# 22_Power_Ext_Discrete_RTC_IC.net
KiCad netlist of a schematic drawn in Altium Designer
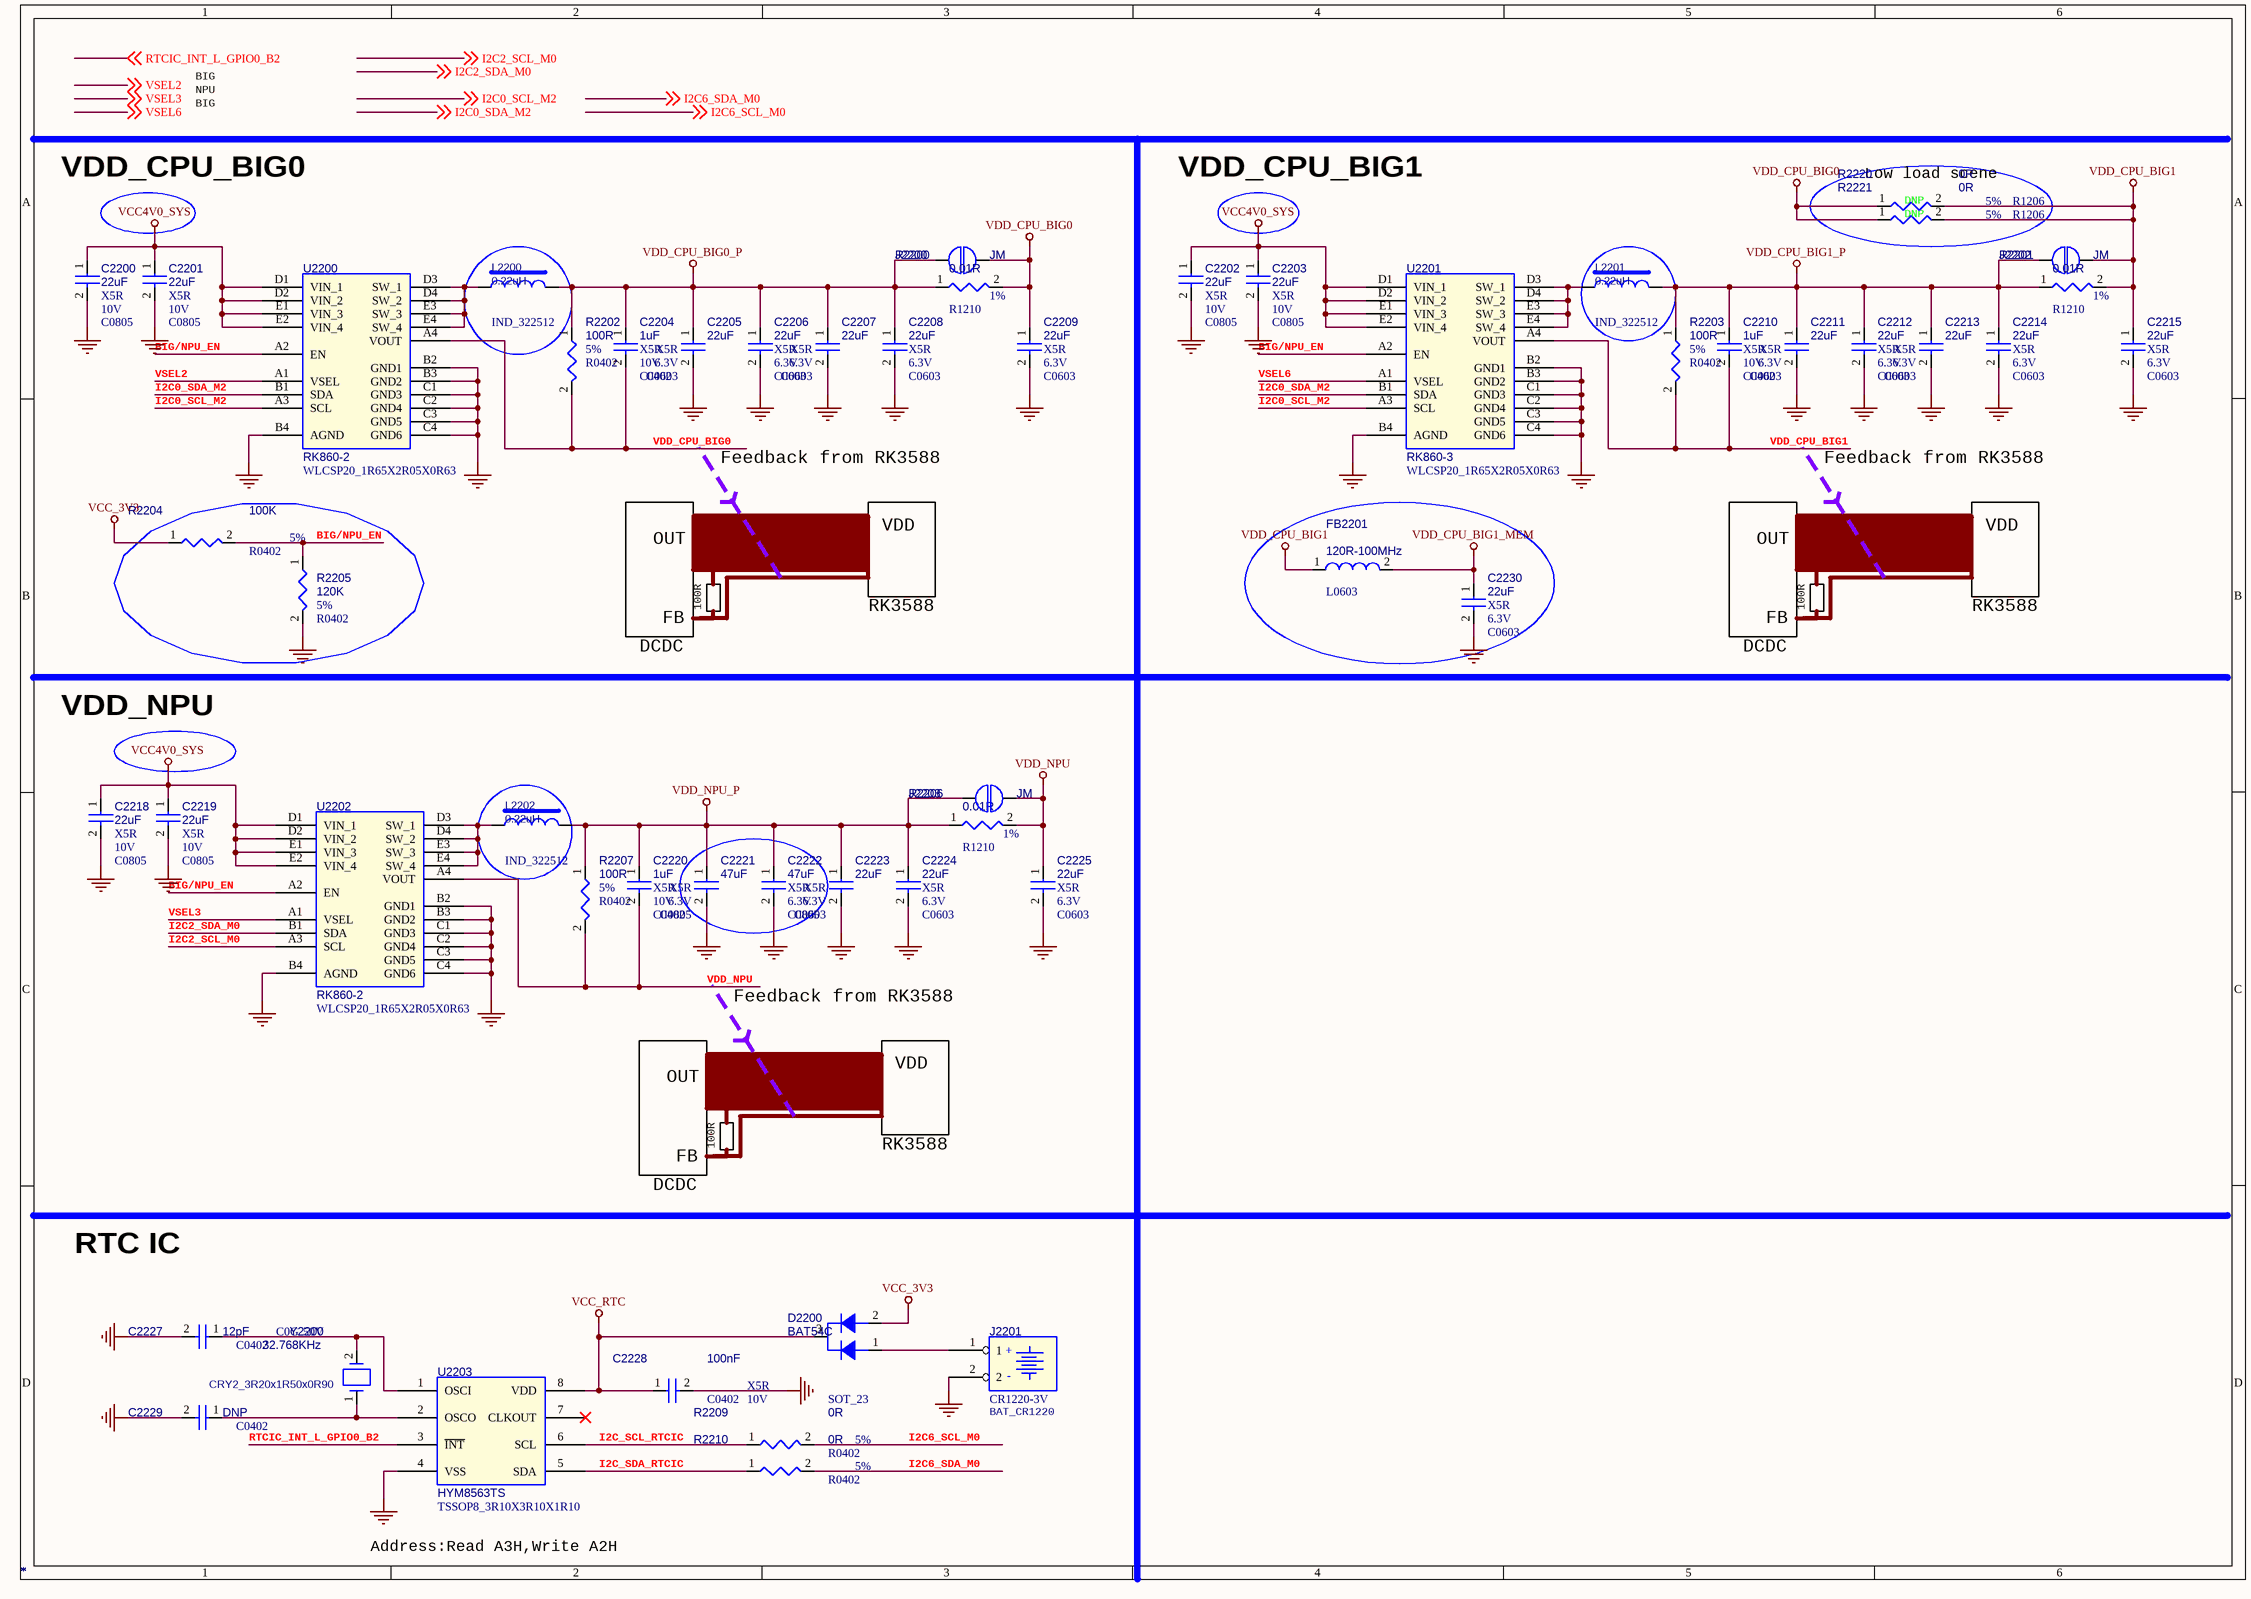
[diagram p0: 22.Power_Ext Discrete_RTC IC.SchDoc]

(export (version "E")
  (design (tool "Eeschema 10.0.6"))
  (components
    (comp (ref "C2200")
      (value "*")
      (footprint "C0805")
      (description "cap,22.00uF,+/-10%,10V,X5R,C0805")
      (fields
        (field (name "VOLTAGE") "10V")
        (field (name "PCB FOOTPRINT") "C0805")
        (field (name "DIELECTRIC") "X5R")
        (field (name "MANUFACTURER") "TDK")
        (field (name "TOLERANCE") "10%")
        (field (name "ALTIUM_UNNAMED_1") "22uF")
        (field (name "CREATED BY") "JJJ")
      )
      (libsource (lib "*") (part "CAP NP"))
    )
    (comp (ref "C2201")
      (value "*")
      (footprint "C0805")
      (description "cap,22.00uF,+/-10%,10V,X5R,C0805")
      (fields
        (field (name "VOLTAGE") "10V")
        (field (name "PCB FOOTPRINT") "C0805")
        (field (name "DIELECTRIC") "X5R")
        (field (name "MANUFACTURER") "TDK")
        (field (name "TOLERANCE") "10%")
        (field (name "ALTIUM_UNNAMED_1") "22uF")
        (field (name "CREATED BY") "JJJ")
      )
      (libsource (lib "*") (part "CAP NP"))
    )
    (comp (ref "C2202")
      (value "*")
      (footprint "C0805")
      (description "cap,22.00uF,+/-10%,10V,X5R,C0805")
      (fields
        (field (name "VOLTAGE") "10V")
        (field (name "PCB FOOTPRINT") "C0805")
        (field (name "DIELECTRIC") "X5R")
        (field (name "MANUFACTURER") "TDK")
        (field (name "TOLERANCE") "10%")
        (field (name "ALTIUM_UNNAMED_1") "22uF")
        (field (name "CREATED BY") "JJJ")
      )
      (libsource (lib "*") (part "CAP NP"))
    )
    (comp (ref "C2203")
      (value "*")
      (footprint "C0805")
      (description "cap,22.00uF,+/-10%,10V,X5R,C0805")
      (fields
        (field (name "VOLTAGE") "10V")
        (field (name "PCB FOOTPRINT") "C0805")
        (field (name "DIELECTRIC") "X5R")
        (field (name "MANUFACTURER") "TDK")
        (field (name "TOLERANCE") "10%")
        (field (name "ALTIUM_UNNAMED_1") "22uF")
        (field (name "CREATED BY") "JJJ")
      )
      (libsource (lib "*") (part "CAP NP"))
    )
    (comp (ref "C2204")
      (value "*")
      (footprint "C0402")
      (description "cap,1.00uF,+/-10%,10V,X5R,C0402")
      (fields
        (field (name "VOLTAGE") "10V")
        (field (name "PCB FOOTPRINT") "C0402")
        (field (name "DIELECTRIC") "X5R")
        (field (name "TOLERANCE") "10%")
        (field (name "MANUFACTURER") "TDK")
        (field (name "ALTIUM_UNNAMED_1") "1uF")
        (field (name "CREATED BY") "JJJ")
      )
      (libsource (lib "*") (part "CAP NP"))
    )
    (comp (ref "C2205")
      (value "*")
      (footprint "C0603")
      (description "cap,22.00uF,+/-20%,6.3V,X5R,C0603")
      (fields
        (field (name "VOLTAGE") "6.3V")
        (field (name "PCB FOOTPRINT") "C0603")
        (field (name "DIELECTRIC") "X5R")
        (field (name "TOLERANCE") "20%")
        (field (name "MANUFACTURER") "TDK")
        (field (name "ALTIUM_UNNAMED_1") "22uF")
        (field (name "CREATED BY") "JJJ")
      )
      (libsource (lib "*") (part "CAP NP"))
    )
    (comp (ref "C2206")
      (value "*")
      (footprint "C0603")
      (description "cap,22.00uF,+/-20%,6.3V,X5R,C0603")
      (fields
        (field (name "VOLTAGE") "6.3V")
        (field (name "PCB FOOTPRINT") "C0603")
        (field (name "DIELECTRIC") "X5R")
        (field (name "MANUFACTURER") "TDK")
        (field (name "TOLERANCE") "20%")
        (field (name "ALTIUM_UNNAMED_1") "22uF")
        (field (name "CREATED BY") "JJJ")
      )
      (libsource (lib "*") (part "CAP NP"))
    )
    (comp (ref "C2207")
      (value "*")
      (footprint "C0603")
      (description "cap,22.00uF,+/-20%,6.3V,X5R,C0603")
      (fields
        (field (name "VOLTAGE") "6.3V")
        (field (name "PCB FOOTPRINT") "C0603")
        (field (name "DIELECTRIC") "X5R")
        (field (name "MANUFACTURER") "TDK")
        (field (name "TOLERANCE") "20%")
        (field (name "ALTIUM_UNNAMED_1") "22uF")
        (field (name "CREATED BY") "JJJ")
      )
      (libsource (lib "*") (part "CAP NP"))
    )
    (comp (ref "C2208")
      (value "*")
      (footprint "C0603")
      (description "cap,22.00uF,+/-20%,6.3V,X5R,C0603")
      (fields
        (field (name "VOLTAGE") "6.3V")
        (field (name "PCB FOOTPRINT") "C0603")
        (field (name "DIELECTRIC") "X5R")
        (field (name "MANUFACTURER") "TDK")
        (field (name "TOLERANCE") "20%")
        (field (name "ALTIUM_UNNAMED_1") "22uF")
        (field (name "CREATED BY") "JJJ")
      )
      (libsource (lib "*") (part "CAP NP"))
    )
    (comp (ref "C2209")
      (value "*")
      (footprint "C0603")
      (description "cap,22.00uF,+/-20%,6.3V,X5R,C0603")
      (fields
        (field (name "VOLTAGE") "6.3V")
        (field (name "PCB FOOTPRINT") "C0603")
        (field (name "DIELECTRIC") "X5R")
        (field (name "TOLERANCE") "20%")
        (field (name "MANUFACTURER") "TDK")
        (field (name "ALTIUM_UNNAMED_1") "22uF")
        (field (name "CREATED BY") "JJJ")
      )
      (libsource (lib "*") (part "CAP NP"))
    )
    (comp (ref "C2210")
      (value "*")
      (footprint "C0402")
      (description "cap,1.00uF,+/-10%,10V,X5R,C0402")
      (fields
        (field (name "VOLTAGE") "10V")
        (field (name "PCB FOOTPRINT") "C0402")
        (field (name "DIELECTRIC") "X5R")
        (field (name "TOLERANCE") "10%")
        (field (name "MANUFACTURER") "TDK")
        (field (name "ALTIUM_UNNAMED_1") "1uF")
        (field (name "CREATED BY") "JJJ")
      )
      (libsource (lib "*") (part "CAP NP"))
    )
    (comp (ref "C2211")
      (value "*")
      (footprint "C0603")
      (description "cap,22.00uF,+/-20%,6.3V,X5R,C0603")
      (fields
        (field (name "VOLTAGE") "6.3V")
        (field (name "PCB FOOTPRINT") "C0603")
        (field (name "DIELECTRIC") "X5R")
        (field (name "TOLERANCE") "20%")
        (field (name "MANUFACTURER") "TDK")
        (field (name "ALTIUM_UNNAMED_1") "22uF")
        (field (name "CREATED BY") "JJJ")
      )
      (libsource (lib "*") (part "CAP NP"))
    )
    (comp (ref "C2212")
      (value "*")
      (footprint "C0603")
      (description "cap,22.00uF,+/-20%,6.3V,X5R,C0603")
      (fields
        (field (name "VOLTAGE") "6.3V")
        (field (name "PCB FOOTPRINT") "C0603")
        (field (name "DIELECTRIC") "X5R")
        (field (name "MANUFACTURER") "TDK")
        (field (name "TOLERANCE") "20%")
        (field (name "ALTIUM_UNNAMED_1") "22uF")
        (field (name "CREATED BY") "JJJ")
      )
      (libsource (lib "*") (part "CAP NP"))
    )
    (comp (ref "C2213")
      (value "*")
      (footprint "C0603")
      (description "cap,22.00uF,+/-20%,6.3V,X5R,C0603")
      (fields
        (field (name "VOLTAGE") "6.3V")
        (field (name "PCB FOOTPRINT") "C0603")
        (field (name "DIELECTRIC") "X5R")
        (field (name "MANUFACTURER") "TDK")
        (field (name "TOLERANCE") "20%")
        (field (name "ALTIUM_UNNAMED_1") "22uF")
        (field (name "CREATED BY") "JJJ")
      )
      (libsource (lib "*") (part "CAP NP"))
    )
    (comp (ref "C2214")
      (value "*")
      (footprint "C0603")
      (description "cap,22.00uF,+/-20%,6.3V,X5R,C0603")
      (fields
        (field (name "VOLTAGE") "6.3V")
        (field (name "PCB FOOTPRINT") "C0603")
        (field (name "DIELECTRIC") "X5R")
        (field (name "MANUFACTURER") "TDK")
        (field (name "TOLERANCE") "20%")
        (field (name "ALTIUM_UNNAMED_1") "22uF")
        (field (name "CREATED BY") "JJJ")
      )
      (libsource (lib "*") (part "CAP NP"))
    )
    (comp (ref "C2215")
      (value "*")
      (footprint "C0603")
      (description "cap,22.00uF,+/-20%,6.3V,X5R,C0603")
      (fields
        (field (name "VOLTAGE") "6.3V")
        (field (name "PCB FOOTPRINT") "C0603")
        (field (name "DIELECTRIC") "X5R")
        (field (name "TOLERANCE") "20%")
        (field (name "MANUFACTURER") "TDK")
        (field (name "ALTIUM_UNNAMED_1") "22uF")
        (field (name "CREATED BY") "JJJ")
      )
      (libsource (lib "*") (part "CAP NP"))
    )
    (comp (ref "C2218")
      (value "*")
      (footprint "C0805")
      (description "cap,22.00uF,+/-10%,10V,X5R,C0805")
      (fields
        (field (name "VOLTAGE") "10V")
        (field (name "PCB FOOTPRINT") "C0805")
        (field (name "DIELECTRIC") "X5R")
        (field (name "TOLERANCE") "10%")
        (field (name "MANUFACTURER") "TDK")
        (field (name "ALTIUM_UNNAMED_1") "22uF")
        (field (name "CREATED BY") "JJJ")
      )
      (libsource (lib "*") (part "CAP NP"))
    )
    (comp (ref "C2219")
      (value "*")
      (footprint "C0805")
      (description "cap,22.00uF,+/-10%,10V,X5R,C0805")
      (fields
        (field (name "VOLTAGE") "10V")
        (field (name "PCB FOOTPRINT") "C0805")
        (field (name "DIELECTRIC") "X5R")
        (field (name "TOLERANCE") "10%")
        (field (name "MANUFACTURER") "TDK")
        (field (name "ALTIUM_UNNAMED_1") "22uF")
        (field (name "CREATED BY") "JJJ")
      )
      (libsource (lib "*") (part "CAP NP"))
    )
    (comp (ref "C2220")
      (value "*")
      (footprint "C0402")
      (description "cap,1.00uF,+/-10%,10V,X5R,C0402")
      (fields
        (field (name "VOLTAGE") "10V")
        (field (name "PCB FOOTPRINT") "C0402")
        (field (name "DIELECTRIC") "X5R")
        (field (name "MANUFACTURER") "TDK")
        (field (name "TOLERANCE") "10%")
        (field (name "ALTIUM_UNNAMED_1") "1uF")
        (field (name "CREATED BY") "JJJ")
      )
      (libsource (lib "*") (part "CAP NP"))
    )
    (comp (ref "C2221")
      (value "*")
      (footprint "C0805")
      (description "cap,47.00uF,+/-20%,6.3V,X5R,C0805")
      (fields
        (field (name "VOLTAGE") "6.3V")
        (field (name "PCB FOOTPRINT") "C0805")
        (field (name "DIELECTRIC") "X5R")
        (field (name "MANUFACTURER") "TDK")
        (field (name "TOLERANCE") "20%")
        (field (name "ALTIUM_UNNAMED_1") "47uF")
        (field (name "CREATED BY") "JJJ")
      )
      (libsource (lib "*") (part "CAP NP"))
    )
    (comp (ref "C2222")
      (value "*")
      (footprint "C0805")
      (description "cap,47.00uF,+/-20%,6.3V,X5R,C0805")
      (fields
        (field (name "VOLTAGE") "6.3V")
        (field (name "PCB FOOTPRINT") "C0805")
        (field (name "DIELECTRIC") "X5R")
        (field (name "TOLERANCE") "20%")
        (field (name "MANUFACTURER") "TDK")
        (field (name "ALTIUM_UNNAMED_1") "47uF")
        (field (name "CREATED BY") "JJJ")
      )
      (libsource (lib "*") (part "CAP NP"))
    )
    (comp (ref "C2223")
      (value "*")
      (footprint "C0603")
      (description "cap,22.00uF,+/-20%,6.3V,X5R,C0603")
      (fields
        (field (name "VOLTAGE") "6.3V")
        (field (name "PCB FOOTPRINT") "C0603")
        (field (name "DIELECTRIC") "X5R")
        (field (name "TOLERANCE") "20%")
        (field (name "MANUFACTURER") "TDK")
        (field (name "ALTIUM_UNNAMED_1") "22uF")
        (field (name "CREATED BY") "JJJ")
      )
      (libsource (lib "*") (part "CAP NP"))
    )
    (comp (ref "C2224")
      (value "*")
      (footprint "C0603")
      (description "cap,22.00uF,+/-20%,6.3V,X5R,C0603")
      (fields
        (field (name "VOLTAGE") "6.3V")
        (field (name "PCB FOOTPRINT") "C0603")
        (field (name "DIELECTRIC") "X5R")
        (field (name "TOLERANCE") "20%")
        (field (name "MANUFACTURER") "TDK")
        (field (name "ALTIUM_UNNAMED_1") "22uF")
        (field (name "CREATED BY") "JJJ")
      )
      (libsource (lib "*") (part "CAP NP"))
    )
    (comp (ref "C2225")
      (value "*")
      (footprint "C0603")
      (description "cap,22.00uF,+/-20%,6.3V,X5R,C0603")
      (fields
        (field (name "VOLTAGE") "6.3V")
        (field (name "PCB FOOTPRINT") "C0603")
        (field (name "DIELECTRIC") "X5R")
        (field (name "TOLERANCE") "20%")
        (field (name "MANUFACTURER") "TDK")
        (field (name "ALTIUM_UNNAMED_1") "22uF")
        (field (name "CREATED BY") "JJJ")
      )
      (libsource (lib "*") (part "CAP NP"))
    )
    (comp (ref "C2227")
      (value "*")
      (footprint "C0402")
      (description "cap,12.00pF,+/-5%,50V,C0G,C0402")
      (fields
        (field (name "VOLTAGE") "50V")
        (field (name "PCB FOOTPRINT") "C0402")
        (field (name "DIELECTRIC") "C0G")
        (field (name "TOLERANCE") "5%")
        (field (name "MANUFACTURER") "TDK")
        (field (name "ALTIUM_UNNAMED_1") "12pF")
        (field (name "CREATED BY") "JJJ")
      )
      (libsource (lib "*") (part "CAP NP"))
    )
    (comp (ref "C2228")
      (value "*")
      (footprint "C0402")
      (description "cap,100.00nF,+/-10%,10V,X5R,C0402")
      (fields
        (field (name "VOLTAGE") "10V")
        (field (name "PCB FOOTPRINT") "C0402")
        (field (name "DIELECTRIC") "X5R")
        (field (name "TOLERANCE") "10%")
        (field (name "MANUFACTURER") "TDK")
        (field (name "ALTIUM_UNNAMED_1") "100nF")
        (field (name "CREATED BY") "JJJ")
      )
      (libsource (lib "*") (part "CAP NP"))
    )
    (comp (ref "C2229")
      (value "*")
      (footprint "C0402")
      (description "Did Not Place.")
      (fields
        (field (name "PCB FOOTPRINT") "C0402")
        (field (name "ALTIUM_UNNAMED_1") "DNP")
        (field (name "CREATED BY") "JJJ")
      )
      (libsource (lib "*") (part "CAP NP"))
    )
    (comp (ref "C2230")
      (value "*")
      (footprint "C0603")
      (description "cap,22.00uF,+/-20%,6.3V,X5R,C0603")
      (fields
        (field (name "VOLTAGE") "6.3V")
        (field (name "PCB FOOTPRINT") "C0603")
        (field (name "DIELECTRIC") "X5R")
        (field (name "TOLERANCE") "20%")
        (field (name "MANUFACTURER") "TDK")
        (field (name "ALTIUM_UNNAMED_1") "22uF")
        (field (name "CREATED BY") "JJJ")
      )
      (libsource (lib "*") (part "CAP NP"))
    )
    (comp (ref "D2200")
      (value "*")
      (footprint "SOT_23")
      (description "Dual Schottky barrierЈ¬BAT54C SOT-23 Schottky Barrier")
      (fields
        (field (name "PCB FOOTPRINT") "SOT_23")
        (field (name "MANUFACTURER") "і¤µз")
        (field (name "ALTIUM_UNNAMED_1") "BAT54C")
        (field (name "CREATED BY") "JJJ")
      )
      (libsource (lib "*") (part "DIODE Double"))
    )
    (comp (ref "FB2201")
      (value "*")
      (footprint "L0603")
      (description "BEAD,120R@100MHz,current=2000mA,0603")
      (fields
        (field (name "TOLERANCE") "25%")
        (field (name "PCB FOOTPRINT") "L0603")
        (field (name "MANUFACTURER") "Murata")
        (field (name "ALTIUM_UNNAMED_1") "120R-100MHz")
        (field (name "CREATED BY") "DZS")
      )
      (libsource (lib "*") (part "BEAD"))
    )
    (comp (ref "J2200")
      (value "*")
      (footprint "OPEN")
      (fields (field (name "ALTIUM_UNNAMED_1") "JM"))
      (libsource (lib "*") (part "JM_0"))
    )
    (comp (ref "J2201")
      (value "*")
      (footprint "BATTERY-20MM")
      (fields (field (name "PCB FOOTPRINT") "BAT_CR1220") (field (name "ALTIUM_UNNAMED_1") "CR1220-3V"))
      (libsource (lib "*") (part "CON_BATTERY-20MM"))
    )
    (comp (ref "J2202")
      (value "*")
      (footprint "OPEN")
      (fields (field (name "ALTIUM_UNNAMED_1") "JM"))
      (libsource (lib "*") (part "JM_0"))
    )
    (comp (ref "J2203")
      (value "*")
      (footprint "OPEN")
      (fields (field (name "ALTIUM_UNNAMED_1") "JM"))
      (libsource (lib "*") (part "JM_0"))
    )
    (comp (ref "L2200")
      (value "*")
      (footprint "IND_322512")
      (description "Power Inductor,0.22uH,20%,IND_322512")
      (fields
        (field (name "PCB FOOTPRINT") "IND_322512")
        (field (name "TOLERANCE") "0.2")
        (field (name "MANUFACTURER") "TDK")
        (field (name "ALTIUM_UNNAMED_1") "0.22uH")
        (field (name "CREATED BY") "YWQ")
      )
      (libsource (lib "*") (part "INDUCTORS OF FERRITE_Dup1"))
    )
    (comp (ref "L2201")
      (value "*")
      (footprint "IND_322512")
      (description "Power Inductor,0.22uH,20%,IND_322512")
      (fields
        (field (name "PCB FOOTPRINT") "IND_322512")
        (field (name "TOLERANCE") "0.2")
        (field (name "MANUFACTURER") "TDK")
        (field (name "ALTIUM_UNNAMED_1") "0.22uH")
        (field (name "CREATED BY") "YWQ")
      )
      (libsource (lib "*") (part "INDUCTORS OF FERRITE_Dup1"))
    )
    (comp (ref "L2202")
      (value "*")
      (footprint "IND_322512")
      (description "Power Inductor,0.22uH,20%,IND_322512")
      (fields
        (field (name "PCB FOOTPRINT") "IND_322512")
        (field (name "MANUFACTURER") "TDK")
        (field (name "TOLERANCE") "0.2")
        (field (name "ALTIUM_UNNAMED_1") "0.22uH")
        (field (name "CREATED BY") "YWQ")
      )
      (libsource (lib "*") (part "INDUCTORS OF FERRITE_Dup1"))
    )
    (comp (ref "R2200")
      (value "*")
      (footprint "R0402")
      (description "єсД¤µНЧиЦµµзЧи,0R01,+/-1%,R1210,1/2W.")
      (fields
        (field (name "PCB FOOTPRINT") "R1210")
        (field (name "TOLERANCE") "1%")
        (field (name "MANUFACTURER") "YAGEO")
        (field (name "ALTIUM_UNNAMED_1") "0.01R")
        (field (name "CREATED BY") "YTL")
      )
      (libsource (lib "*") (part "RESISTOR_Dup1"))
    )
    (comp (ref "R2201")
      (value "*")
      (footprint "R0402")
      (description "єсД¤µНЧиЦµµзЧи,0R01,+/-1%,R1210,1/2W.")
      (fields
        (field (name "PCB FOOTPRINT") "R1210")
        (field (name "TOLERANCE") "1%")
        (field (name "MANUFACTURER") "YAGEO")
        (field (name "ALTIUM_UNNAMED_1") "0.01R")
        (field (name "CREATED BY") "YTL")
      )
      (libsource (lib "*") (part "RESISTOR_Dup1"))
    )
    (comp (ref "R2202")
      (value "*")
      (footprint "R0402")
      (description "НЁУГєсД¤µзЧи,100R,+/-5%,R0402,1/16W.")
      (fields
        (field (name "PCB FOOTPRINT") "R0402")
        (field (name "TOLERANCE") "5%")
        (field (name "MANUFACTURER") "YAGEO")
        (field (name "ALTIUM_UNNAMED_1") "100R")
        (field (name "CREATED BY") "YTL")
      )
      (libsource (lib "*") (part "RESISTOR_Dup1"))
    )
    (comp (ref "R2203")
      (value "*")
      (footprint "R0402")
      (description "НЁУГєсД¤µзЧи,100R,+/-5%,R0402,1/16W.")
      (fields
        (field (name "PCB FOOTPRINT") "R0402")
        (field (name "TOLERANCE") "5%")
        (field (name "MANUFACTURER") "YAGEO")
        (field (name "ALTIUM_UNNAMED_1") "100R")
        (field (name "CREATED BY") "YTL")
      )
      (libsource (lib "*") (part "RESISTOR_Dup1"))
    )
    (comp (ref "R2204")
      (value "*")
      (footprint "R0402")
      (description "НЁУГєсД¤µзЧи,100K,+/-5%,R0402,1/16W.")
      (fields
        (field (name "PCB FOOTPRINT") "R0402")
        (field (name "TOLERANCE") "5%")
        (field (name "MANUFACTURER") "YAGEO")
        (field (name "ALTIUM_UNNAMED_1") "100K")
        (field (name "CREATED BY") "YTL")
      )
      (libsource (lib "*") (part "RESISTOR_Dup1"))
    )
    (comp (ref "R2205")
      (value "*")
      (footprint "R0402")
      (description "НЁУГєсД¤µзЧи,120K,+/-5%,R0402,1/16W.")
      (fields
        (field (name "PCB FOOTPRINT") "R0402")
        (field (name "TOLERANCE") "5%")
        (field (name "MANUFACTURER") "YAGEO")
        (field (name "ALTIUM_UNNAMED_1") "120K")
        (field (name "CREATED BY") "YTL")
      )
      (libsource (lib "*") (part "RESISTOR_Dup1"))
    )
    (comp (ref "R2206")
      (value "*")
      (footprint "R0402")
      (description "єсД¤µНЧиЦµµзЧи,0R01,+/-1%,R1210,1/2W.")
      (fields
        (field (name "PCB FOOTPRINT") "R1210")
        (field (name "TOLERANCE") "1%")
        (field (name "MANUFACTURER") "YAGEO")
        (field (name "ALTIUM_UNNAMED_1") "0.01R")
        (field (name "CREATED BY") "YTL")
      )
      (libsource (lib "*") (part "RESISTOR_Dup1"))
    )
    (comp (ref "R2207")
      (value "*")
      (footprint "R0402")
      (description "НЁУГєсД¤µзЧи,100R,+/-5%,R0402,1/16W.")
      (fields
        (field (name "PCB FOOTPRINT") "R0402")
        (field (name "TOLERANCE") "5%")
        (field (name "MANUFACTURER") "YAGEO")
        (field (name "ALTIUM_UNNAMED_1") "100R")
        (field (name "CREATED BY") "YTL")
      )
      (libsource (lib "*") (part "RESISTOR_Dup1"))
    )
    (comp (ref "R2209")
      (value "*")
      (footprint "R0402")
      (description "НЁУГєсД¤µзЧи,0R,+/-5%,R0402,1/16W.")
      (fields
        (field (name "PCB FOOTPRINT") "R0402")
        (field (name "TOLERANCE") "5%")
        (field (name "MANUFACTURER") "YAGEO")
        (field (name "ALTIUM_UNNAMED_1") "0R")
        (field (name "CREATED BY") "YTL")
      )
      (libsource (lib "*") (part "RESISTOR_Dup1"))
    )
    (comp (ref "R2210")
      (value "*")
      (footprint "R0402")
      (description "НЁУГєсД¤µзЧи,0R,+/-5%,R0402,1/16W.")
      (fields
        (field (name "PCB FOOTPRINT") "R0402")
        (field (name "TOLERANCE") "5%")
        (field (name "MANUFACTURER") "YAGEO")
        (field (name "ALTIUM_UNNAMED_1") "0R")
        (field (name "CREATED BY") "YTL")
      )
      (libsource (lib "*") (part "RESISTOR_Dup1"))
    )
    (comp (ref "R2220")
      (value "*")
      (footprint "R0402")
      (description "НЁУГєсД¤µзЧи,0R,+/-5%,R1206,1/4W.")
      (fields
        (field (name "PCB FOOTPRINT") "R1206")
        (field (name "TOLERANCE") "5%")
        (field (name "MANUFACTURER") "YAGEO")
        (field (name "OPTION") "DNP")
        (field (name "ALTIUM_UNNAMED_1") "0R")
        (field (name "CREATED BY") "YTL")
      )
      (libsource (lib "*") (part "RESISTOR_Dup1"))
    )
    (comp (ref "R2221")
      (value "*")
      (footprint "R0402")
      (description "НЁУГєсД¤µзЧи,0R,+/-5%,R1206,1/4W.")
      (fields
        (field (name "PCB FOOTPRINT") "R1206")
        (field (name "TOLERANCE") "5%")
        (field (name "OPTION") "DNP")
        (field (name "MANUFACTURER") "YAGEO")
        (field (name "ALTIUM_UNNAMED_1") "0R")
        (field (name "CREATED BY") "YTL")
      )
      (libsource (lib "*") (part "RESISTOR_Dup1"))
    )
    (comp (ref "U2200")
      (value "*")
      (footprint "WLCSP-20")
      (description "I2C-ADDR 42HЈ»Vout 0.5-1.5VЈ»Default Vout 0.8VЈ»Step 6.25mVЈ»Die_ID 0XA;")
      (fields
        (field (name "PCB FOOTPRINT") "WLCSP20_1R65X2R05X0R63")
        (field (name "MANUFACTURER") "Rockchip (ИрРѕОў)")
        (field (name "ALTIUM_UNNAMED_1") "RK860-2")
        (field (name "CREATED BY") "YWQ")
      )
      (libsource (lib "*") (part "DCDC_RK860"))
    )
    (comp (ref "U2201")
      (value "*")
      (footprint "WLCSP-20")
      (description "I2C-ADDR 43HЈ»Vout 0.5-1.5VЈ»Default Vout 0.8VЈ»Step 6.25mVЈ»Die_ID 0XA;")
      (fields
        (field (name "PCB FOOTPRINT") "WLCSP20_1R65X2R05X0R63")
        (field (name "MANUFACTURER") "Rockchip (ИрРѕОў)")
        (field (name "ALTIUM_UNNAMED_1") "RK860-3")
        (field (name "CREATED BY") "YWQ")
      )
      (libsource (lib "*") (part "DCDC_RK860"))
    )
    (comp (ref "U2202")
      (value "*")
      (footprint "WLCSP-20")
      (description "I2C-ADDR 42HЈ»Vout 0.5-1.5VЈ»Default Vout 0.8VЈ»Step 6.25mVЈ»Die_ID 0XA;")
      (fields
        (field (name "PCB FOOTPRINT") "WLCSP20_1R65X2R05X0R63")
        (field (name "MANUFACTURER") "Rockchip (ИрРѕОў)")
        (field (name "ALTIUM_UNNAMED_1") "RK860-2")
        (field (name "CREATED BY") "YWQ")
      )
      (libsource (lib "*") (part "DCDC_RK860"))
    )
    (comp (ref "U2203")
      (value "*")
      (footprint "TSSOP8_3R10X3R10X1R10")
      (description "I2C Real Time Clock/Calendar")
      (fields
        (field (name "PCB FOOTPRINT") "TSSOP8_3R10X3R10X1R10")
        (field (name "MANUFACTURER") "HaoyuЈЁк»кЕОўµзЧУЈ©")
        (field (name "ALTIUM_UNNAMED_1") "HYM8563TS")
        (field (name "CREATED BY") "JJJ")
      )
      (libsource (lib "*") (part "RTC_HYM8563"))
    )
    (comp (ref "Y2200")
      (value "*")
      (footprint "CRY2_3R20x1R50x0R90")
      (description "ОЮФґѕ§ХсЈ¬32.768KHz,ЎА20ppmЈ¬12.5pF")
      (fields
        (field (name "PCB FOOTPRINT") "CRY2_3R20x1R50x0R90")
        (field (name "MANUFACTURER") "TKD(М©ѕ§)")
        (field (name "ALTIUM_UNNAMED_1") "32.768KHz")
        (field (name "CREATED BY") "YWQ")
      )
      (libsource (lib "*") (part "CRYSTAL_2P"))
    )
  )
  (nets
    (net (code "1") (name "/BIG{slash}NPU_EN") (class "Default")
      (node (ref "R2204") (pin "2") (pinfunction "2_2") (pintype "passive"))
      (node (ref "R2205") (pin "1") (pinfunction "1_1") (pintype "passive"))
      (node (ref "U2200") (pin "A2") (pinfunction "EN_A2") (pintype "passive"))
      (node (ref "U2201") (pin "A2") (pinfunction "EN_A2") (pintype "passive"))
      (node (ref "U2202") (pin "A2") (pinfunction "EN_A2") (pintype "passive"))
    )
    (net (code "2") (name "/I2C_SCL_RTCIC") (class "Default")
      (node (ref "R2209") (pin "1") (pinfunction "1_1") (pintype "passive"))
      (node (ref "U2203") (pin "6") (pinfunction "SCL_6") (pintype "passive"))
    )
    (net (code "3") (name "/I2C_SDA_RTCIC") (class "Default")
      (node (ref "R2210") (pin "1") (pinfunction "1_1") (pintype "passive"))
      (node (ref "U2203") (pin "5") (pinfunction "SDA_5") (pintype "passive"))
    )
    (net (code "4") (name "GND") (class "Default")
      (node (ref "C2200") (pin "2") (pinfunction "2_2") (pintype "passive"))
      (node (ref "C2201") (pin "2") (pinfunction "2_2") (pintype "passive"))
      (node (ref "C2202") (pin "2") (pinfunction "2_2") (pintype "passive"))
      (node (ref "C2203") (pin "2") (pinfunction "2_2") (pintype "passive"))
      (node (ref "C2205") (pin "2") (pinfunction "2_2") (pintype "passive"))
      (node (ref "C2206") (pin "2") (pinfunction "2_2") (pintype "passive"))
      (node (ref "C2207") (pin "2") (pinfunction "2_2") (pintype "passive"))
      (node (ref "C2208") (pin "2") (pinfunction "2_2") (pintype "passive"))
      (node (ref "C2209") (pin "2") (pinfunction "2_2") (pintype "passive"))
      (node (ref "C2211") (pin "2") (pinfunction "2_2") (pintype "passive"))
      (node (ref "C2212") (pin "2") (pinfunction "2_2") (pintype "passive"))
      (node (ref "C2213") (pin "2") (pinfunction "2_2") (pintype "passive"))
      (node (ref "C2214") (pin "2") (pinfunction "2_2") (pintype "passive"))
      (node (ref "C2215") (pin "2") (pinfunction "2_2") (pintype "passive"))
      (node (ref "C2218") (pin "2") (pinfunction "2_2") (pintype "passive"))
      (node (ref "C2219") (pin "2") (pinfunction "2_2") (pintype "passive"))
      (node (ref "C2221") (pin "2") (pinfunction "2_2") (pintype "passive"))
      (node (ref "C2222") (pin "2") (pinfunction "2_2") (pintype "passive"))
      (node (ref "C2223") (pin "2") (pinfunction "2_2") (pintype "passive"))
      (node (ref "C2224") (pin "2") (pinfunction "2_2") (pintype "passive"))
      (node (ref "C2225") (pin "2") (pinfunction "2_2") (pintype "passive"))
      (node (ref "C2227") (pin "2") (pinfunction "2_2") (pintype "passive"))
      (node (ref "C2228") (pin "2") (pinfunction "2_2") (pintype "passive"))
      (node (ref "C2229") (pin "2") (pinfunction "2_2") (pintype "passive"))
      (node (ref "C2230") (pin "2") (pinfunction "2_2") (pintype "passive"))
      (node (ref "J2201") (pin "2") (pinfunction "2_2") (pintype "passive"))
      (node (ref "R2205") (pin "2") (pinfunction "2_2") (pintype "passive"))
      (node (ref "U2200") (pin "B2") (pinfunction "GND1_B2") (pintype "passive"))
      (node (ref "U2200") (pin "B3") (pinfunction "GND2_B3") (pintype "passive"))
      (node (ref "U2200") (pin "B4") (pinfunction "AGND_B4") (pintype "passive"))
      (node (ref "U2200") (pin "C1") (pinfunction "GND3_C1") (pintype "passive"))
      (node (ref "U2200") (pin "C2") (pinfunction "GND4_C2") (pintype "passive"))
      (node (ref "U2200") (pin "C3") (pinfunction "GND5_C3") (pintype "passive"))
      (node (ref "U2200") (pin "C4") (pinfunction "GND6_C4") (pintype "passive"))
      (node (ref "U2201") (pin "B2") (pinfunction "GND1_B2") (pintype "passive"))
      (node (ref "U2201") (pin "B3") (pinfunction "GND2_B3") (pintype "passive"))
      (node (ref "U2201") (pin "B4") (pinfunction "AGND_B4") (pintype "passive"))
      (node (ref "U2201") (pin "C1") (pinfunction "GND3_C1") (pintype "passive"))
      (node (ref "U2201") (pin "C2") (pinfunction "GND4_C2") (pintype "passive"))
      (node (ref "U2201") (pin "C3") (pinfunction "GND5_C3") (pintype "passive"))
      (node (ref "U2201") (pin "C4") (pinfunction "GND6_C4") (pintype "passive"))
      (node (ref "U2202") (pin "B2") (pinfunction "GND1_B2") (pintype "passive"))
      (node (ref "U2202") (pin "B3") (pinfunction "GND2_B3") (pintype "passive"))
      (node (ref "U2202") (pin "B4") (pinfunction "AGND_B4") (pintype "passive"))
      (node (ref "U2202") (pin "C1") (pinfunction "GND3_C1") (pintype "passive"))
      (node (ref "U2202") (pin "C2") (pinfunction "GND4_C2") (pintype "passive"))
      (node (ref "U2202") (pin "C3") (pinfunction "GND5_C3") (pintype "passive"))
      (node (ref "U2202") (pin "C4") (pinfunction "GND6_C4") (pintype "passive"))
      (node (ref "U2203") (pin "4") (pinfunction "VSS_4") (pintype "passive"))
    )
    (net (code "5") (name "I2C0_SCL_M2") (class "Default")
      (node (ref "U2200") (pin "A3") (pinfunction "SCL_A3") (pintype "passive"))
      (node (ref "U2201") (pin "A3") (pinfunction "SCL_A3") (pintype "passive"))
    )
    (net (code "6") (name "I2C0_SDA_M2") (class "Default")
      (node (ref "U2200") (pin "B1") (pinfunction "SDA_B1") (pintype "passive"))
      (node (ref "U2201") (pin "B1") (pinfunction "SDA_B1") (pintype "passive"))
    )
    (net (code "7") (name "I2C2_SCL_M0") (class "Default")
      (node (ref "U2202") (pin "A3") (pinfunction "SCL_A3") (pintype "passive"))
    )
    (net (code "8") (name "I2C2_SDA_M0") (class "Default")
      (node (ref "U2202") (pin "B1") (pinfunction "SDA_B1") (pintype "passive"))
    )
    (net (code "9") (name "I2C6_SCL_M0") (class "Default")
      (node (ref "R2209") (pin "2") (pinfunction "2_2") (pintype "passive"))
    )
    (net (code "10") (name "I2C6_SDA_M0") (class "Default")
      (node (ref "R2210") (pin "2") (pinfunction "2_2") (pintype "passive"))
    )
    (net (code "11") (name "Net-(D2200-A1)") (class "Default")
      (node (ref "D2200") (pin "1") (pinfunction "A1_1") (pintype "passive"))
      (node (ref "J2201") (pin "1") (pinfunction "1_1") (pintype "passive"))
    )
    (net (code "12") (name "Net-(U2200-SW_1)") (class "Default")
      (node (ref "L2200") (pin "1") (pinfunction "1_1") (pintype "passive"))
      (node (ref "U2200") (pin "D3") (pinfunction "SW_1_D3") (pintype "passive"))
      (node (ref "U2200") (pin "D4") (pinfunction "SW_2_D4") (pintype "passive"))
      (node (ref "U2200") (pin "E3") (pinfunction "SW_3_E3") (pintype "passive"))
      (node (ref "U2200") (pin "E4") (pinfunction "SW_4_E4") (pintype "passive"))
    )
    (net (code "13") (name "Net-(U2201-SW_1)") (class "Default")
      (node (ref "L2201") (pin "1") (pinfunction "1_1") (pintype "passive"))
      (node (ref "U2201") (pin "D3") (pinfunction "SW_1_D3") (pintype "passive"))
      (node (ref "U2201") (pin "D4") (pinfunction "SW_2_D4") (pintype "passive"))
      (node (ref "U2201") (pin "E3") (pinfunction "SW_3_E3") (pintype "passive"))
      (node (ref "U2201") (pin "E4") (pinfunction "SW_4_E4") (pintype "passive"))
    )
    (net (code "14") (name "Net-(U2202-SW_1)") (class "Default")
      (node (ref "L2202") (pin "1") (pinfunction "1_1") (pintype "passive"))
      (node (ref "U2202") (pin "D3") (pinfunction "SW_1_D3") (pintype "passive"))
      (node (ref "U2202") (pin "D4") (pinfunction "SW_2_D4") (pintype "passive"))
      (node (ref "U2202") (pin "E3") (pinfunction "SW_3_E3") (pintype "passive"))
      (node (ref "U2202") (pin "E4") (pinfunction "SW_4_E4") (pintype "passive"))
    )
    (net (code "15") (name "Net-(U2203-OSCI)") (class "Default")
      (node (ref "C2227") (pin "1") (pinfunction "1_1") (pintype "passive"))
      (node (ref "U2203") (pin "1") (pinfunction "OSCI_1") (pintype "passive"))
      (node (ref "Y2200") (pin "2") (pinfunction "2_2") (pintype "passive"))
    )
    (net (code "16") (name "Net-(U2203-OSCO)") (class "Default")
      (node (ref "C2229") (pin "1") (pinfunction "1_1") (pintype "passive"))
      (node (ref "U2203") (pin "2") (pinfunction "OSCO_2") (pintype "passive"))
      (node (ref "Y2200") (pin "1") (pinfunction "1_1") (pintype "passive"))
    )
    (net (code "17") (name "RTCIC_INT_L_GPIO0_B2") (class "Default")
      (node (ref "U2203") (pin "3") (pinfunction "~{INT}_3") (pintype "passive"))
    )
    (net (code "18") (name "VCC4V0_SYS") (class "Default")
      (node (ref "C2200") (pin "1") (pinfunction "1_1") (pintype "passive"))
      (node (ref "C2201") (pin "1") (pinfunction "1_1") (pintype "passive"))
      (node (ref "C2202") (pin "1") (pinfunction "1_1") (pintype "passive"))
      (node (ref "C2203") (pin "1") (pinfunction "1_1") (pintype "passive"))
      (node (ref "C2218") (pin "1") (pinfunction "1_1") (pintype "passive"))
      (node (ref "C2219") (pin "1") (pinfunction "1_1") (pintype "passive"))
      (node (ref "U2200") (pin "D1") (pinfunction "VIN_1_D1") (pintype "passive"))
      (node (ref "U2200") (pin "D2") (pinfunction "VIN_2_D2") (pintype "passive"))
      (node (ref "U2200") (pin "E1") (pinfunction "VIN_3_E1") (pintype "passive"))
      (node (ref "U2200") (pin "E2") (pinfunction "VIN_4_E2") (pintype "passive"))
      (node (ref "U2201") (pin "D1") (pinfunction "VIN_1_D1") (pintype "passive"))
      (node (ref "U2201") (pin "D2") (pinfunction "VIN_2_D2") (pintype "passive"))
      (node (ref "U2201") (pin "E1") (pinfunction "VIN_3_E1") (pintype "passive"))
      (node (ref "U2201") (pin "E2") (pinfunction "VIN_4_E2") (pintype "passive"))
      (node (ref "U2202") (pin "D1") (pinfunction "VIN_1_D1") (pintype "passive"))
      (node (ref "U2202") (pin "D2") (pinfunction "VIN_2_D2") (pintype "passive"))
      (node (ref "U2202") (pin "E1") (pinfunction "VIN_3_E1") (pintype "passive"))
      (node (ref "U2202") (pin "E2") (pinfunction "VIN_4_E2") (pintype "passive"))
    )
    (net (code "19") (name "VCC_3V3") (class "Default")
      (node (ref "D2200") (pin "2") (pinfunction "A2_2") (pintype "passive"))
      (node (ref "R2204") (pin "1") (pinfunction "1_1") (pintype "passive"))
    )
    (net (code "20") (name "VCC_RTC") (class "Default")
      (node (ref "C2228") (pin "1") (pinfunction "1_1") (pintype "passive"))
      (node (ref "D2200") (pin "3") (pinfunction "K_3") (pintype "passive"))
      (node (ref "U2203") (pin "8") (pinfunction "VDD_8") (pintype "passive"))
    )
    (net (code "21") (name "VDD_CPU_BIG0") (class "Default")
      (node (ref "C2204") (pin "2") (pinfunction "2_2") (pintype "passive"))
      (node (ref "C2209") (pin "1") (pinfunction "1_1") (pintype "passive"))
      (node (ref "J2200") (pin "2") (pinfunction "2_2") (pintype "passive"))
      (node (ref "R2200") (pin "2") (pinfunction "2_2") (pintype "passive"))
      (node (ref "R2202") (pin "2") (pinfunction "2_2") (pintype "passive"))
      (node (ref "R2220") (pin "1") (pinfunction "1_1") (pintype "passive"))
      (node (ref "R2221") (pin "1") (pinfunction "1_1") (pintype "passive"))
      (node (ref "U2200") (pin "A4") (pinfunction "VOUT_A4") (pintype "passive"))
    )
    (net (code "22") (name "VDD_CPU_BIG0_P") (class "Default")
      (node (ref "C2204") (pin "1") (pinfunction "1_1") (pintype "passive"))
      (node (ref "C2205") (pin "1") (pinfunction "1_1") (pintype "passive"))
      (node (ref "C2206") (pin "1") (pinfunction "1_1") (pintype "passive"))
      (node (ref "C2207") (pin "1") (pinfunction "1_1") (pintype "passive"))
      (node (ref "C2208") (pin "1") (pinfunction "1_1") (pintype "passive"))
      (node (ref "J2200") (pin "1") (pinfunction "1_1") (pintype "passive"))
      (node (ref "L2200") (pin "2") (pinfunction "2_2") (pintype "passive"))
      (node (ref "R2200") (pin "1") (pinfunction "1_1") (pintype "passive"))
      (node (ref "R2202") (pin "1") (pinfunction "1_1") (pintype "passive"))
    )
    (net (code "23") (name "VDD_CPU_BIG1") (class "Default")
      (node (ref "C2210") (pin "2") (pinfunction "2_2") (pintype "passive"))
      (node (ref "C2215") (pin "1") (pinfunction "1_1") (pintype "passive"))
      (node (ref "FB2201") (pin "1") (pinfunction "1_1") (pintype "passive"))
      (node (ref "J2202") (pin "2") (pinfunction "2_2") (pintype "passive"))
      (node (ref "R2201") (pin "2") (pinfunction "2_2") (pintype "passive"))
      (node (ref "R2203") (pin "2") (pinfunction "2_2") (pintype "passive"))
      (node (ref "R2220") (pin "2") (pinfunction "2_2") (pintype "passive"))
      (node (ref "R2221") (pin "2") (pinfunction "2_2") (pintype "passive"))
      (node (ref "U2201") (pin "A4") (pinfunction "VOUT_A4") (pintype "passive"))
    )
    (net (code "24") (name "VDD_CPU_BIG1_MEM") (class "Default")
      (node (ref "C2230") (pin "1") (pinfunction "1_1") (pintype "passive"))
      (node (ref "FB2201") (pin "2") (pinfunction "2_2") (pintype "passive"))
    )
    (net (code "25") (name "VDD_CPU_BIG1_P") (class "Default")
      (node (ref "C2210") (pin "1") (pinfunction "1_1") (pintype "passive"))
      (node (ref "C2211") (pin "1") (pinfunction "1_1") (pintype "passive"))
      (node (ref "C2212") (pin "1") (pinfunction "1_1") (pintype "passive"))
      (node (ref "C2213") (pin "1") (pinfunction "1_1") (pintype "passive"))
      (node (ref "C2214") (pin "1") (pinfunction "1_1") (pintype "passive"))
      (node (ref "J2202") (pin "1") (pinfunction "1_1") (pintype "passive"))
      (node (ref "L2201") (pin "2") (pinfunction "2_2") (pintype "passive"))
      (node (ref "R2201") (pin "1") (pinfunction "1_1") (pintype "passive"))
      (node (ref "R2203") (pin "1") (pinfunction "1_1") (pintype "passive"))
    )
    (net (code "26") (name "VDD_NPU") (class "Default")
      (node (ref "C2220") (pin "2") (pinfunction "2_2") (pintype "passive"))
      (node (ref "C2225") (pin "1") (pinfunction "1_1") (pintype "passive"))
      (node (ref "J2203") (pin "2") (pinfunction "2_2") (pintype "passive"))
      (node (ref "R2206") (pin "2") (pinfunction "2_2") (pintype "passive"))
      (node (ref "R2207") (pin "2") (pinfunction "2_2") (pintype "passive"))
      (node (ref "U2202") (pin "A4") (pinfunction "VOUT_A4") (pintype "passive"))
    )
    (net (code "27") (name "VDD_NPU_P") (class "Default")
      (node (ref "C2220") (pin "1") (pinfunction "1_1") (pintype "passive"))
      (node (ref "C2221") (pin "1") (pinfunction "1_1") (pintype "passive"))
      (node (ref "C2222") (pin "1") (pinfunction "1_1") (pintype "passive"))
      (node (ref "C2223") (pin "1") (pinfunction "1_1") (pintype "passive"))
      (node (ref "C2224") (pin "1") (pinfunction "1_1") (pintype "passive"))
      (node (ref "J2203") (pin "1") (pinfunction "1_1") (pintype "passive"))
      (node (ref "L2202") (pin "2") (pinfunction "2_2") (pintype "passive"))
      (node (ref "R2206") (pin "1") (pinfunction "1_1") (pintype "passive"))
      (node (ref "R2207") (pin "1") (pinfunction "1_1") (pintype "passive"))
    )
    (net (code "28") (name "VSEL2") (class "Default")
      (node (ref "U2200") (pin "A1") (pinfunction "VSEL_A1") (pintype "passive"))
    )
    (net (code "29") (name "VSEL3") (class "Default")
      (node (ref "U2202") (pin "A1") (pinfunction "VSEL_A1") (pintype "passive"))
    )
    (net (code "30") (name "VSEL6") (class "Default")
      (node (ref "U2201") (pin "A1") (pinfunction "VSEL_A1") (pintype "passive"))
    )
    (net (code "31") (name "unconnected-(U2203-CLKOUT-Pad7)") (class "Default")
      (node (ref "U2203") (pin "7") (pinfunction "CLKOUT_7") (pintype "passive+no_connect"))
    )
  )
)
